# BLDC_Page2.net
KiCad netlist of a schematic drawn in Altium Designer
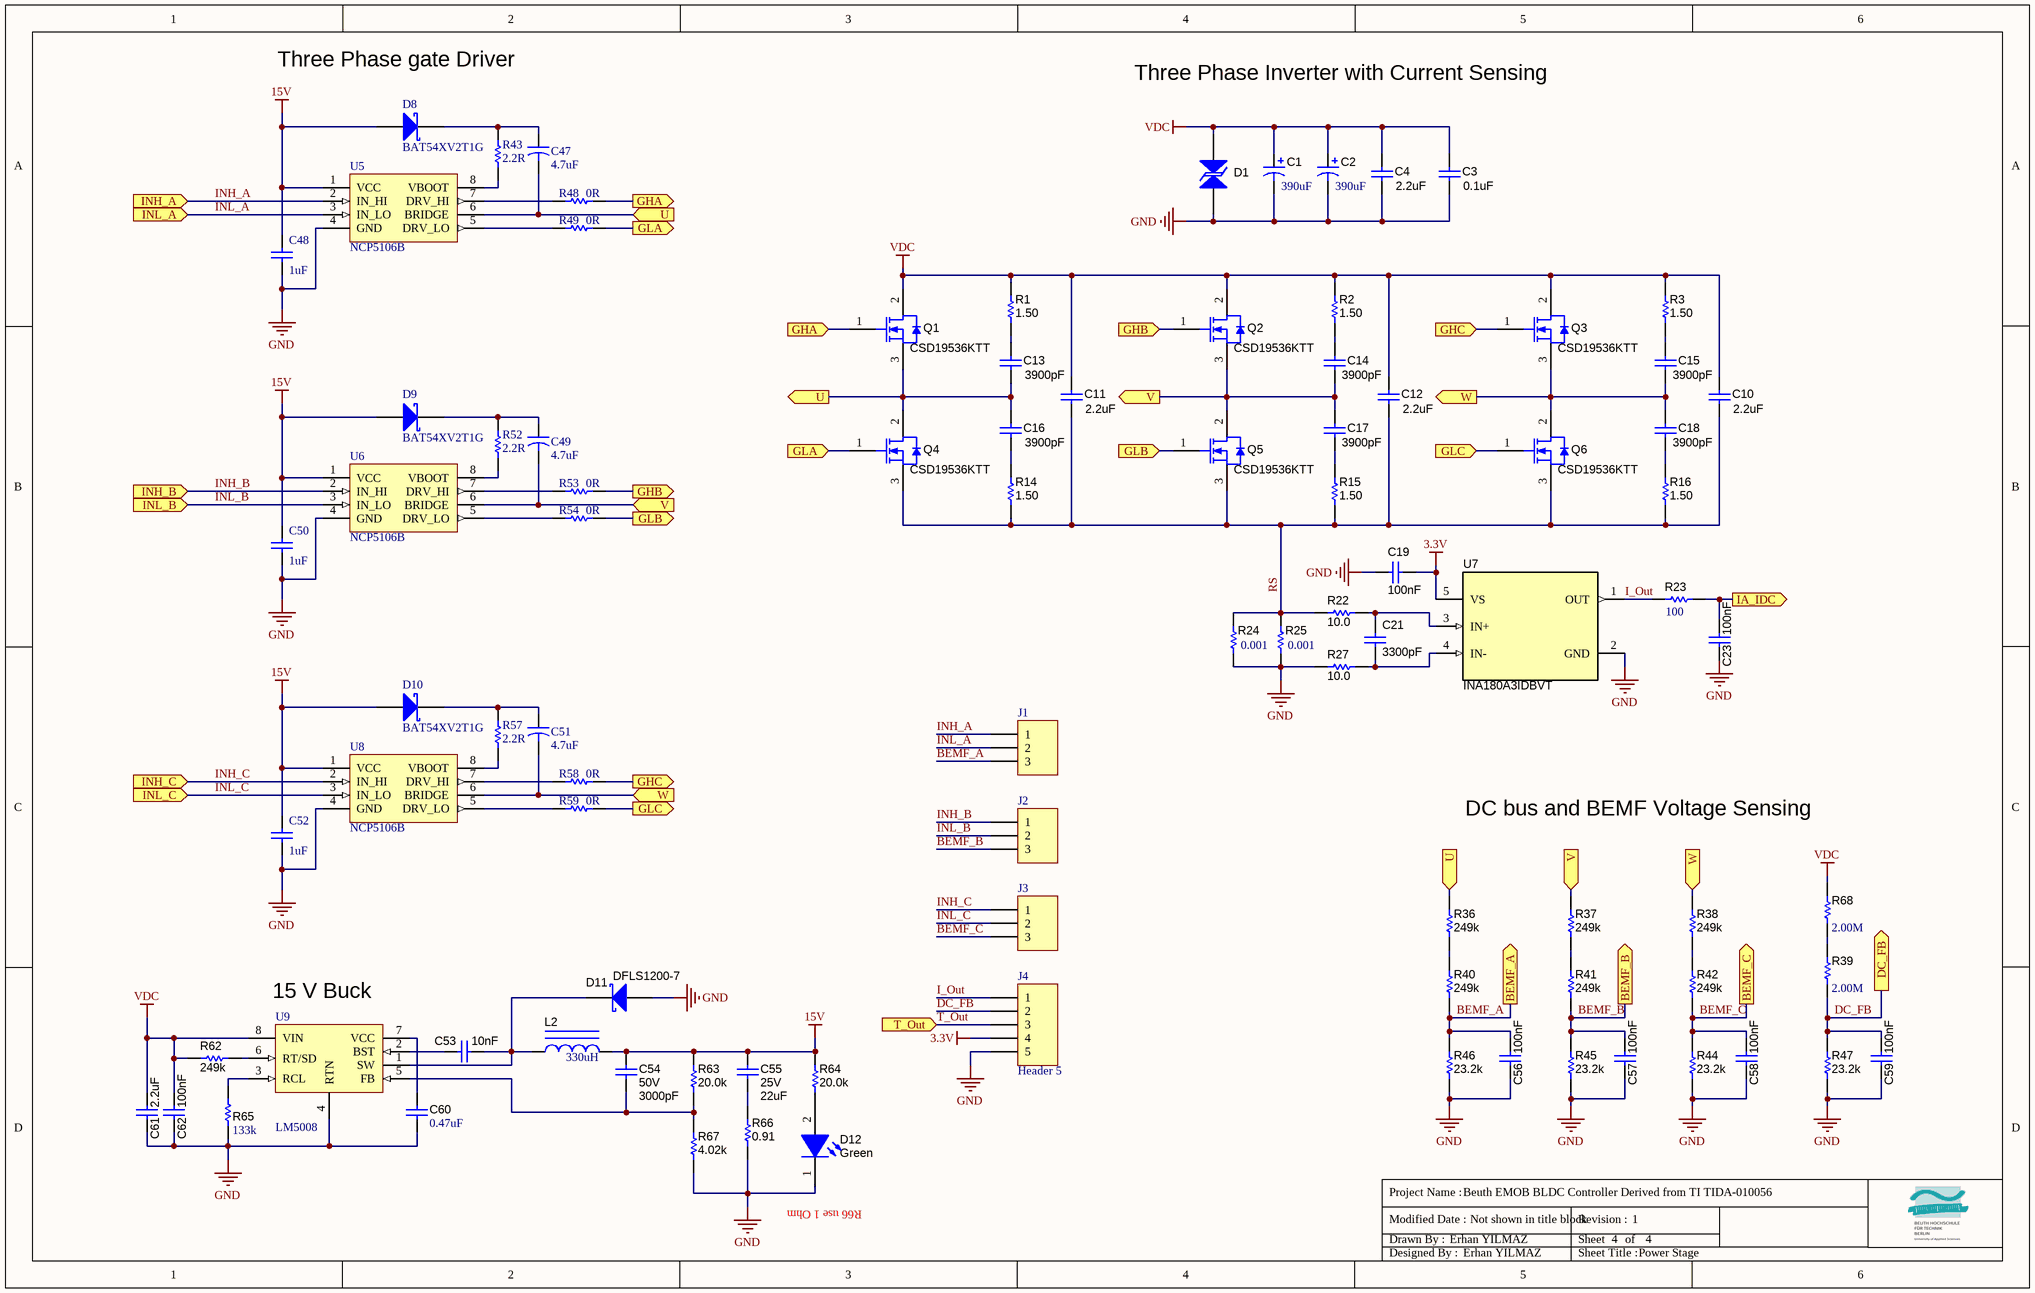
[diagram p0: BLDC_Page2.SchDoc]

(export (version "E")
  (design (tool "Eeschema 10.0.6"))
  (components
    (comp (ref "C1")
      (value "EEU-FS2A391")
      (footprint "YXJ_1600x2500")
      (description "CAP ALUM 390UF 20% 100V THRUHOLE")
      (fields
        (field (name "MANUFACTURER") "Panasonic Electronic Components")
        (field (name "VALUEDISPLAYED") "390uF")
        (field (name "PUBLISHER") "Texas Instruments")
      )
      (libsource (lib "Altium Vault - TI") (part "Cap_Polarized"))
    )
    (comp (ref "C2")
      (value "EEU-FS2A391")
      (footprint "YXJ_1600x2500")
      (description "CAP ALUM 390UF 20% 100V THRUHOLE")
      (fields
        (field (name "MANUFACTURER") "Panasonic Electronic Components")
        (field (name "VALUEDISPLAYED") "390uF")
        (field (name "PUBLISHER") "Texas Instruments")
      )
      (libsource (lib "Altium Vault - TI") (part "Cap_Polarized"))
    )
    (comp (ref "C3")
      (value "C3216X7R2A104K160AA")
      (footprint "1206")
      (description "CAP, CERM, 0.1 uF, 100 V, +/- 10%, X7R, 1206")
      (fields
        (field (name "MANUFACTURER") "TDK")
        (field (name "VALUEDISPLAYED") "0.1uF")
        (field (name "PUBLISHER") "Texas Instruments")
      )
      (libsource (lib "Altium Vault - TI") (part "Capacitor"))
    )
    (comp (ref "C4")
      (value "CL31B225KCHSNNE")
      (footprint "1206")
      (description "CAP CER 2.2UF 100V X7R 1206")
      (fields
        (field (name "MANUFACTURER") "Samsung Electro-Mechanics")
        (field (name "VALUEDISPLAYED") "2.2uF")
        (field (name "PUBLISHER") "Texas Instruments")
      )
      (libsource (lib "Altium Vault - TI") (part "Capacitor"))
    )
    (comp (ref "C10")
      (value "CL31B225KCHSNNE")
      (footprint "1206")
      (description "CAP CER 2.2UF 100V X7R 1206")
      (fields
        (field (name "MANUFACTURER") "Samsung Electro-Mechanics")
        (field (name "VALUEDISPLAYED") "2.2uF")
        (field (name "PUBLISHER") "Texas Instruments")
      )
      (libsource (lib "Altium Vault - TI") (part "Capacitor"))
    )
    (comp (ref "C11")
      (value "CL31B225KCHSNNE")
      (footprint "1206")
      (description "CAP CER 2.2UF 100V X7R 1206")
      (fields
        (field (name "MANUFACTURER") "Samsung Electro-Mechanics")
        (field (name "VALUEDISPLAYED") "2.2uF")
        (field (name "PUBLISHER") "Texas Instruments")
      )
      (libsource (lib "Altium Vault - TI") (part "Capacitor"))
    )
    (comp (ref "C12")
      (value "CL31B225KCHSNNE")
      (footprint "1206")
      (description "CAP CER 2.2UF 100V X7R 1206")
      (fields
        (field (name "MANUFACTURER") "Samsung Electro-Mechanics")
        (field (name "VALUEDISPLAYED") "2.2uF")
        (field (name "PUBLISHER") "Texas Instruments")
      )
      (libsource (lib "Altium Vault - TI") (part "Capacitor"))
    )
    (comp (ref "C13")
      (value "12061C392KAZ2A")
      (footprint "1206")
      (description "CAP CER 3900PF 100V X7R 1206")
      (fields
        (field (name "MANUFACTURER") "AVX Corporation")
        (field (name "VALUEDISPLAYED") "3900pF")
        (field (name "PUBLISHER") "Texas Instruments")
      )
      (libsource (lib "Altium Vault - TI") (part "Capacitor"))
    )
    (comp (ref "C14")
      (value "12061C392KAZ2A")
      (footprint "1206")
      (description "CAP CER 3900PF 100V X7R 1206")
      (fields
        (field (name "MANUFACTURER") "AVX Corporation")
        (field (name "VALUEDISPLAYED") "3900pF")
        (field (name "PUBLISHER") "Texas Instruments")
      )
      (libsource (lib "Altium Vault - TI") (part "Capacitor"))
    )
    (comp (ref "C15")
      (value "12061C392KAZ2A")
      (footprint "1206")
      (description "CAP CER 3900PF 100V X7R 1206")
      (fields
        (field (name "MANUFACTURER") "AVX Corporation")
        (field (name "VALUEDISPLAYED") "3900pF")
        (field (name "PUBLISHER") "Texas Instruments")
      )
      (libsource (lib "Altium Vault - TI") (part "Capacitor"))
    )
    (comp (ref "C16")
      (value "12061C392KAZ2A")
      (footprint "1206")
      (description "CAP CER 3900PF 100V X7R 1206")
      (fields
        (field (name "MANUFACTURER") "AVX Corporation")
        (field (name "VALUEDISPLAYED") "3900pF")
        (field (name "PUBLISHER") "Texas Instruments")
      )
      (libsource (lib "Altium Vault - TI") (part "Capacitor"))
    )
    (comp (ref "C17")
      (value "12061C392KAZ2A")
      (footprint "1206")
      (description "CAP CER 3900PF 100V X7R 1206")
      (fields
        (field (name "MANUFACTURER") "AVX Corporation")
        (field (name "VALUEDISPLAYED") "3900pF")
        (field (name "PUBLISHER") "Texas Instruments")
      )
      (libsource (lib "Altium Vault - TI") (part "Capacitor"))
    )
    (comp (ref "C18")
      (value "12061C392KAZ2A")
      (footprint "1206")
      (description "CAP CER 3900PF 100V X7R 1206")
      (fields
        (field (name "MANUFACTURER") "AVX Corporation")
        (field (name "VALUEDISPLAYED") "3900pF")
        (field (name "PUBLISHER") "Texas Instruments")
      )
      (libsource (lib "Altium Vault - TI") (part "Capacitor"))
    )
    (comp (ref "C19")
      (value "GRM1885C1H302JA01D")
      (footprint "0603")
      (description "CAP, CERM, 100 nF, 100 V, +/- 5%, C0G/NP0, 0603")
      (fields
        (field (name "MANUFACTURER") "MuRata")
        (field (name "VALUEDISPLAYED") "100nF")
        (field (name "PUBLISHER") "Texas Instruments")
      )
      (libsource (lib "Altium Vault - TI") (part "Capacitor"))
    )
    (comp (ref "C21")
      (value "3300pF")
      (footprint "0603")
      (description "CAP, CERM, 3300 pF, 50 V, +/- 10%, X7R, 0603")
      (fields
        (field (name "MANUFACTURER") "MuRata")
        (field (name "PARTNUMBER") "GRM155R71H332KA01D")
        (field (name "PUBLISHER") "Texas Instruments")
      )
      (libsource (lib "Altium Vault - TI") (part "Capacitor"))
    )
    (comp (ref "C23")
      (value "GRM1885C1H302JA01D")
      (footprint "0603")
      (description "CAP, CERM, 100 nF, 100 V, +/- 5%, C0G/NP0, 0603")
      (fields
        (field (name "MANUFACTURER") "MuRata")
        (field (name "VALUEDISPLAYED") "100nF")
        (field (name "PUBLISHER") "Texas Instruments")
      )
      (libsource (lib "Altium Vault - TI") (part "Capacitor"))
    )
    (comp (ref "C47")
      (value "4.7uF")
      (footprint "0805_HV")
      (description "4.7uF 25V Tantalum SMD Capacitor")
      (fields (field (name "MANUFACTURER") "AVX") (field (name "PUBLISHER") "Altium Limited"))
      (libsource (lib "Miscellaneous Devices") (part "Cap2"))
    )
    (comp (ref "C48")
      (value "1uF")
      (footprint "0603")
      (description "1uF %10 35V 0603")
      (fields (field (name "PUBLISHER") "Altium Limited"))
      (libsource (lib "Miscellaneous Devices") (part "Cap Semi"))
    )
    (comp (ref "C49")
      (value "4.7uF")
      (footprint "0805_HV")
      (description "4.7uF 25V Tantalum SMD Capacitor")
      (fields (field (name "MANUFACTURER") "AVX") (field (name "PUBLISHER") "Altium Limited"))
      (libsource (lib "Miscellaneous Devices") (part "Cap2"))
    )
    (comp (ref "C50")
      (value "1uF")
      (footprint "0603")
      (description "1uF %10 35V  0603")
      (fields (field (name "PUBLISHER") "Altium Limited"))
      (libsource (lib "Miscellaneous Devices") (part "Cap Semi"))
    )
    (comp (ref "C51")
      (value "4.7uF")
      (footprint "0805_HV")
      (description "4.7uF 25V Tantalum SMD Capacitor")
      (fields (field (name "MANUFACTURER") "AVX") (field (name "PUBLISHER") "Altium Limited"))
      (libsource (lib "Miscellaneous Devices") (part "Cap2"))
    )
    (comp (ref "C52")
      (value "1uF")
      (footprint "0603")
      (description "1uF %10 35V  0603")
      (fields (field (name "PUBLISHER") "Altium Limited"))
      (libsource (lib "Miscellaneous Devices") (part "Cap Semi"))
    )
    (comp (ref "C53")
      (value "885012206114")
      (footprint "0603")
      (description "CAP, CERM, 0.01 µF, 100 V,+/- 10%, X7R, 0603")
      (fields (field (name "MANUFACTURER") "Wurth Elektronik") (field (name "CAP_F") "10nF"))
      (libsource (lib "Altium Vault - TI") (part "Capacitor"))
    )
    (comp (ref "C54")
      (value "CAP, CERM, 3000 pF, 50 V, +/- 5%, C0G/NP0, 0603")
      (footprint "0603")
      (fields
        (field (name "MANUFACTURER") "MuRata")
        (field (name "PARTNUMBER") "GRM1885C1H302JA01D")
        (field (name "VDC_V") "50V")
        (field (name "VALUEDISPLAYED") "3000pF")
        (field (name "PUBLISHER") "Texas Instruments")
      )
      (libsource (lib "Altium Vault - TI") (part "Capacitor"))
    )
    (comp (ref "C55")
      (value "C2012X7R1H225K125AC")
      (footprint "1210_280")
      (description "CAP, CERM, 22 uF, 25 V, +/- 10%, X7R, 1210")
      (fields
        (field (name "MANUFACTURER") "TDK")
        (field (name "VDC_V") "25V")
        (field (name "VALUEDISPLAYED") "22uF")
        (field (name "PUBLISHER") "Texas Instruments")
      )
      (libsource (lib "Altium Vault - TI") (part "Capacitor"))
    )
    (comp (ref "C56")
      (value "GRM1885C1H302JA01D")
      (footprint "0603")
      (description "CAP, CERM, 100 nF, 100 V, +/- 5%, C0G/NP0, 0603")
      (fields
        (field (name "MANUFACTURER") "MuRata")
        (field (name "VALUEDISPLAYED") "100nF")
        (field (name "PUBLISHER") "Texas Instruments")
      )
      (libsource (lib "Altium Vault - TI") (part "Capacitor"))
    )
    (comp (ref "C57")
      (value "GRM1885C1H302JA01D")
      (footprint "0603")
      (description "CAP, CERM, 100 nF, 100 V, +/- 5%, C0G/NP0, 0603")
      (fields
        (field (name "MANUFACTURER") "MuRata")
        (field (name "VALUEDISPLAYED") "100nF")
        (field (name "PUBLISHER") "Texas Instruments")
      )
      (libsource (lib "Altium Vault - TI") (part "Capacitor"))
    )
    (comp (ref "C58")
      (value "GRM1885C1H302JA01D")
      (footprint "0603")
      (description "CAP, CERM, 100 nF, 100 V, +/- 5%, C0G/NP0, 0603")
      (fields
        (field (name "MANUFACTURER") "MuRata")
        (field (name "VALUEDISPLAYED") "100nF")
        (field (name "PUBLISHER") "Texas Instruments")
      )
      (libsource (lib "Altium Vault - TI") (part "Capacitor"))
    )
    (comp (ref "C59")
      (value "GRM1885C1H302JA01D")
      (footprint "0603")
      (description "CAP, CERM, 100 nF, 100 V, +/- 5%, C0G/NP0, 0603")
      (fields
        (field (name "MANUFACTURER") "MuRata")
        (field (name "VALUEDISPLAYED") "100nF")
        (field (name "PUBLISHER") "Texas Instruments")
      )
      (libsource (lib "Altium Vault - TI") (part "Capacitor"))
    )
    (comp (ref "C60")
      (value "CGB2A1X5R1C474K033BC")
      (footprint "0603")
      (description "CAP CER 0.47UF 16V X5R 0603")
      (fields
        (field (name "MANUFACTURER") "TDK Corporation")
        (field (name "VALUEDISPLAYED") "0.47uF")
        (field (name "PUBLISHER") "Texas Instruments")
      )
      (libsource (lib "Altium Vault - TI") (part "Capacitor"))
    )
    (comp (ref "C61")
      (value "C2012X7R1H225K125AC")
      (footprint "1206")
      (description "CAP, CERM, 2.2 uF, 100 V, +/- 10%, X7R, 1206")
      (fields
        (field (name "MANUFACTURER") "TDK")
        (field (name "VALUEDISPLAYED") "2.2uF")
        (field (name "PUBLISHER") "Texas Instruments")
      )
      (libsource (lib "Altium Vault - TI") (part "Capacitor"))
    )
    (comp (ref "C62")
      (value "GRM1885C1H302JA01D")
      (footprint "0603")
      (description "CAP, CERM, 100 nF, 100 V, +/- 5%, C0G/NP0, 0603")
      (fields
        (field (name "MANUFACTURER") "MuRata")
        (field (name "VALUEDISPLAYED") "100nF")
        (field (name "PUBLISHER") "Texas Instruments")
      )
      (libsource (lib "Altium Vault - TI") (part "Capacitor"))
    )
    (comp (ref "D1")
      (value "SMBJ70CA-13-F")
      (footprint "SMB-Bi")
      (description "Diode, TVS, Bi, 70 V, SMB")
      (fields (field (name "MANUFACTURER") "Diodes Inc."))
      (libsource (lib "Altium Vault - TI") (part "Diode_TVS_Bi"))
    )
    (comp (ref "D8")
      (value "BAT54XV2T1G")
      (footprint "SOD-523")
      (description "Schottky Diode")
      (fields (field (name "PUBLISHER") "Altium Limited"))
      (libsource (lib "Miscellaneous Devices") (part "D Schottky"))
    )
    (comp (ref "D9")
      (value "BAT54XV2T1G")
      (footprint "BLDC:SOD-523")
      (description "Schottky Diode")
      (fields (field (name "PUBLISHER") "Altium Limited"))
      (libsource (lib "Miscellaneous Devices") (part "D Schottky"))
    )
    (comp (ref "D10")
      (value "BAT54XV2T1G")
      (footprint "SOD-523")
      (description "Schottky Diode")
      (fields (field (name "PUBLISHER") "Altium Limited"))
      (libsource (lib "Miscellaneous Devices") (part "D Schottky"))
    )
    (comp (ref "D11")
      (value "DFLS1200-7")
      (footprint "PowerDI123")
      (description "Diode, Schottky, 200 V, 1 A, PowerDI123")
      (fields (field (name "MANUFACTURER") "Diodes Inc.") (field (name "PUBLISHER") "Texas Instruments"))
      (libsource (lib "Altium Vault - TI") (part "DIODE_SCHOTTKY"))
    )
    (comp (ref "D12")
      (value "Green")
      (footprint "WL-SMCW_GREEN")
      (description "LED, Green, SMD")
      (fields
        (field (name "MANUFACTURER") "Wurth Elektronik")
        (field (name "PARTNUMBER") "150060GS75000")
        (field (name "PUBLISHER") "Texas Instruments")
      )
      (libsource (lib "Altium Vault - TI") (part "LED_A2_K1"))
    )
    (comp (ref "J1")
      (value "Header 3")
      (footprint "HDR1X3")
      (description "Header, 3-Pin")
      (fields (field (name "PUBLISHER") "Altium Limited"))
      (libsource (lib "Miscellaneous Connectors") (part "Header 3"))
    )
    (comp (ref "J2")
      (value "Header 3")
      (footprint "HDR1X3")
      (description "Header, 3-Pin")
      (fields (field (name "PUBLISHER") "Altium Limited"))
      (libsource (lib "Miscellaneous Connectors") (part "Header 3"))
    )
    (comp (ref "J3")
      (value "Header 3")
      (footprint "HDR1X3")
      (description "Header, 3-Pin")
      (fields (field (name "PUBLISHER") "Altium Limited"))
      (libsource (lib "Miscellaneous Connectors") (part "Header 3"))
    )
    (comp (ref "J4")
      (value "Header 5")
      (footprint "HDR1X5")
      (description "Header, 5-Pin")
      (fields (field (name "PUBLISHER") "Altium Limited"))
      (libsource (lib "Miscellaneous Connectors") (part "Header 5"))
    )
    (comp (ref "L2")
      (value "SDR0604-331KL")
      (footprint "SDR0604")
      (description "Inductor, Drum Core, Ferrite, 330 uH, 0.27 A, 2.25 ohm, SMD")
      (fields
        (field (name "MANUFACTURER") "Bourns")
        (field (name "VALUEDISPLAYED") "330uH")
        (field (name "PUBLISHER") "Texas Instruments")
      )
      (libsource (lib "Altium Vault - TI") (part "Inductor_Iron"))
    )
    (comp (ref "Q1")
      (value "CSD19536KTT")
      (footprint "KTT0002A")
      (description "MOSFET, N-CH, 100 V, 200 A, KTT0002A (TO-263-2)")
      (fields (field (name "MANUFACTURER") "Texas Instruments"))
      (libsource (lib "Altium Vault - TI") (part "MOSFET_N_D2G1S3"))
    )
    (comp (ref "Q2")
      (value "CSD19536KTT")
      (footprint "KTT0002A")
      (description "MOSFET, N-CH, 100 V, 200 A, KTT0002A (TO-263-2)")
      (fields (field (name "MANUFACTURER") "Texas Instruments"))
      (libsource (lib "Altium Vault - TI") (part "MOSFET_N_D2G1S3"))
    )
    (comp (ref "Q3")
      (value "CSD19536KTT")
      (footprint "KTT0002A")
      (description "MOSFET, N-CH, 100 V, 200 A, KTT0002A (TO-263-2)")
      (fields (field (name "MANUFACTURER") "Texas Instruments"))
      (libsource (lib "Altium Vault - TI") (part "MOSFET_N_D2G1S3"))
    )
    (comp (ref "Q4")
      (value "CSD19536KTT")
      (footprint "KTT0002A")
      (description "MOSFET, N-CH, 100 V, 200 A, KTT0002A (TO-263-2)")
      (fields (field (name "MANUFACTURER") "Texas Instruments"))
      (libsource (lib "Altium Vault - TI") (part "MOSFET_N_D2G1S3"))
    )
    (comp (ref "Q5")
      (value "CSD19536KTT")
      (footprint "KTT0002A")
      (description "MOSFET, N-CH, 100 V, 200 A, KTT0002A (TO-263-2)")
      (fields (field (name "MANUFACTURER") "Texas Instruments"))
      (libsource (lib "Altium Vault - TI") (part "MOSFET_N_D2G1S3"))
    )
    (comp (ref "Q6")
      (value "CSD19536KTT")
      (footprint "KTT0002A")
      (description "MOSFET, N-CH, 100 V, 200 A, KTT0002A (TO-263-2)")
      (fields (field (name "MANUFACTURER") "Texas Instruments"))
      (libsource (lib "Altium Vault - TI") (part "MOSFET_N_D2G1S3"))
    )
    (comp (ref "R1")
      (value "CRCW12061R50FKEA")
      (footprint "1206")
      (description "RES, 1.50, 1%, 0.25 W, AEC-Q200 Grade 0, 1206")
      (fields (field (name "MANUFACTURER") "Vishay-Dale") (field (name "VALUEDISPLAYED") "1.50"))
      (libsource (lib "Altium Vault - TI") (part "Resistor"))
    )
    (comp (ref "R2")
      (value "CRCW12061R50FKEA")
      (footprint "1206")
      (description "RES, 1.50, 1%, 0.25 W, AEC-Q200 Grade 0, 1206")
      (fields (field (name "MANUFACTURER") "Vishay-Dale") (field (name "VALUEDISPLAYED") "1.50"))
      (libsource (lib "Altium Vault - TI") (part "Resistor"))
    )
    (comp (ref "R3")
      (value "CRCW12061R50FKEA")
      (footprint "1206")
      (description "RES, 1.50, 1%, 0.25 W, AEC-Q200 Grade 0, 1206")
      (fields (field (name "MANUFACTURER") "Vishay-Dale") (field (name "VALUEDISPLAYED") "1.50"))
      (libsource (lib "Altium Vault - TI") (part "Resistor"))
    )
    (comp (ref "R14")
      (value "CRCW12061R50FKEA")
      (footprint "1206")
      (description "RES, 1.50, 1%, 0.25 W, AEC-Q200 Grade 0, 1206")
      (fields (field (name "MANUFACTURER") "Vishay-Dale") (field (name "VALUEDISPLAYED") "1.50"))
      (libsource (lib "Altium Vault - TI") (part "Resistor"))
    )
    (comp (ref "R15")
      (value "CRCW12061R50FKEA")
      (footprint "1206")
      (description "RES, 1.50, 1%, 0.25 W, AEC-Q200 Grade 0, 1206")
      (fields (field (name "MANUFACTURER") "Vishay-Dale") (field (name "VALUEDISPLAYED") "1.50"))
      (libsource (lib "Altium Vault - TI") (part "Resistor"))
    )
    (comp (ref "R16")
      (value "CRCW12061R50FKEA")
      (footprint "1206")
      (description "RES, 1.50, 1%, 0.25 W, AEC-Q200 Grade 0, 1206")
      (fields (field (name "MANUFACTURER") "Vishay-Dale") (field (name "VALUEDISPLAYED") "1.50"))
      (libsource (lib "Altium Vault - TI") (part "Resistor"))
    )
    (comp (ref "R22")
      (value "CRCW040210R0FKED")
      (footprint "0603")
      (description "RES, 10.0, 1%, 0.063 W, AEC-Q200 Grade 0, 0603")
      (fields (field (name "MANUFACTURER") "Vishay-Dale") (field (name "VALUEDISPLAYED") "10.0"))
      (libsource (lib "Altium Vault - TI") (part "Resistor"))
    )
    (comp (ref "R23")
      (value "ERJ-2GEJ101X")
      (footprint "0603")
      (description "RES, 100, 5%, 0.1 W, AEC-Q200 Grade 0, 0603")
      (fields
        (field (name "MANUFACTURER") "Panasonic")
        (field (name "VALUEDISPLAYED") "100")
        (field (name "PUBLISHER") "Texas Instruments")
      )
      (libsource (lib "Altium Vault - TI") (part "Resistor"))
    )
    (comp (ref "R24")
      (value "CRE2512-FZ-R001E-3")
      (footprint "CRE2512-R1_R4")
      (description "RES, 0.001, 1%, 3 W, AEC-Q200 Grade 0, 2512")
      (fields
        (field (name "MANUFACTURER") "Bourns")
        (field (name "VALUEDISPLAYED") "0.001")
        (field (name "PUBLISHER") "Texas Instruments")
      )
      (libsource (lib "Altium Vault - TI") (part "Resistor"))
    )
    (comp (ref "R25")
      (value "0.001")
      (footprint "CRE2512-R1_R4")
      (description "RES, 0.001, 1%, 3 W, AEC-Q200 Grade 0, 2512")
      (fields
        (field (name "MANUFACTURER") "Bourns")
        (field (name "PARTNUMBER") "CRE2512-FZ-R001E-3")
        (field (name "PUBLISHER") "Texas Instruments")
      )
      (libsource (lib "Altium Vault - TI") (part "Resistor"))
    )
    (comp (ref "R27")
      (value "CRCW040210R0FKED")
      (footprint "0603")
      (description "RES, 10.0, 1%, 0.063 W, AEC-Q200 Grade 0, 0603")
      (fields (field (name "MANUFACTURER") "Vishay-Dale") (field (name "VALUEDISPLAYED") "10.0"))
      (libsource (lib "Altium Vault - TI") (part "Resistor"))
    )
    (comp (ref "R36")
      (value "RC0603FR-07249KL")
      (footprint "0603")
      (description "RES SMD 249K OHM 1% 1/16W 0603")
      (fields (field (name "MANUFACTURER") "Yageo") (field (name "VALUEDISPLAYED") "249k"))
      (libsource (lib "Altium Vault - TI") (part "Resistor"))
    )
    (comp (ref "R37")
      (value "RC0603FR-07249KL")
      (footprint "0603")
      (description "RES SMD 249K OHM 1% 1/16W 0603")
      (fields (field (name "MANUFACTURER") "Yageo") (field (name "VALUEDISPLAYED") "249k"))
      (libsource (lib "Altium Vault - TI") (part "Resistor"))
    )
    (comp (ref "R38")
      (value "RC0603FR-07249KL")
      (footprint "0603")
      (description "RES SMD 249K OHM 1% 1/16W 0603")
      (fields (field (name "MANUFACTURER") "Yageo") (field (name "VALUEDISPLAYED") "249k"))
      (libsource (lib "Altium Vault - TI") (part "Resistor"))
    )
    (comp (ref "R39")
      (value "CRCW06032M00FKED")
      (footprint "0603")
      (description "RES, 2.00 M, 1%, 0.063 W, AEC-Q200 Grade 0, 0603")
      (fields
        (field (name "MANUFACTURER") "Vishay-Dale")
        (field (name "PARTNUMBER") "CRCW04022M00FKED")
        (field (name "VALUEDISPLAYED") "2.00M")
      )
      (libsource (lib "Altium Vault - TI") (part "Resistor"))
    )
    (comp (ref "R40")
      (value "RC0603FR-07249KL")
      (footprint "0603")
      (description "RES SMD 249K OHM 1% 1/16W 0603")
      (fields (field (name "MANUFACTURER") "Yageo") (field (name "VALUEDISPLAYED") "249k"))
      (libsource (lib "Altium Vault - TI") (part "Resistor"))
    )
    (comp (ref "R41")
      (value "RC0603FR-07249KL")
      (footprint "0603")
      (description "RES SMD 249K OHM 1% 1/16W 0603")
      (fields (field (name "MANUFACTURER") "Yageo") (field (name "VALUEDISPLAYED") "249k"))
      (libsource (lib "Altium Vault - TI") (part "Resistor"))
    )
    (comp (ref "R42")
      (value "RC0603FR-07249KL")
      (footprint "0603")
      (description "RES SMD 249K OHM 1% 1/16W 0603")
      (fields (field (name "MANUFACTURER") "Yageo") (field (name "VALUEDISPLAYED") "249k"))
      (libsource (lib "Altium Vault - TI") (part "Resistor"))
    )
    (comp (ref "R43")
      (value "2.2R")
      (footprint "0603")
      (description "2.2R SMD 0.33w 0603")
      (fields (field (name "PUBLISHER") "Altium Limited"))
      (libsource (lib "Miscellaneous Devices") (part "Res1"))
    )
    (comp (ref "R44")
      (value "RC0603FR-0723K2L")
      (footprint "0603")
      (description "RES SMD 23.2K OHM 1% 1/16W 0603")
      (fields (field (name "MANUFACTURER") "Yageo") (field (name "VALUEDISPLAYED") "23.2k"))
      (libsource (lib "Altium Vault - TI") (part "Resistor"))
    )
    (comp (ref "R45")
      (value "RC0603FR-0723K2L")
      (footprint "0603")
      (description "RES SMD 23.2K OHM 1% 1/16W 0603")
      (fields (field (name "MANUFACTURER") "Yageo") (field (name "VALUEDISPLAYED") "23.2k"))
      (libsource (lib "Altium Vault - TI") (part "Resistor"))
    )
    (comp (ref "R46")
      (value "RC0603FR-0723K2L")
      (footprint "0603")
      (description "RES SMD 23.2K OHM 1% 1/16W 0603")
      (fields (field (name "MANUFACTURER") "Yageo") (field (name "VALUEDISPLAYED") "23.2k"))
      (libsource (lib "Altium Vault - TI") (part "Resistor"))
    )
    (comp (ref "R47")
      (value "RC0603FR-0723K2L")
      (footprint "0603")
      (description "RES SMD 23.2K OHM 1% 1/16W 0603")
      (fields (field (name "MANUFACTURER") "Yageo") (field (name "VALUEDISPLAYED") "23.2k"))
      (libsource (lib "Altium Vault - TI") (part "Resistor"))
    )
    (comp (ref "R48")
      (value "0R")
      (footprint "0603")
      (description "0R SMD 0.33w 0603")
      (fields (field (name "PUBLISHER") "Altium Limited"))
      (libsource (lib "Miscellaneous Devices") (part "Res1"))
    )
    (comp (ref "R49")
      (value "0R")
      (footprint "0603")
      (description "0R SMD 0.33w 0603")
      (fields (field (name "PUBLISHER") "Altium Limited"))
      (libsource (lib "Miscellaneous Devices") (part "Res1"))
    )
    (comp (ref "R52")
      (value "2.2R")
      (footprint "0603")
      (description "2.2R SMD 0.33w 0603")
      (fields (field (name "PUBLISHER") "Altium Limited"))
      (libsource (lib "Miscellaneous Devices") (part "Res1"))
    )
    (comp (ref "R53")
      (value "0R")
      (footprint "0603")
      (description "0R SMD 0.33w 0603")
      (fields (field (name "PUBLISHER") "Altium Limited"))
      (libsource (lib "Miscellaneous Devices") (part "Res1"))
    )
    (comp (ref "R54")
      (value "0R")
      (footprint "0603")
      (description "0R SMD 0.33w 0603")
      (fields (field (name "PUBLISHER") "Altium Limited"))
      (libsource (lib "Miscellaneous Devices") (part "Res1"))
    )
    (comp (ref "R57")
      (value "2.2R")
      (footprint "0603")
      (description "2.2R SMD 0.33w 0603")
      (fields (field (name "PUBLISHER") "Altium Limited"))
      (libsource (lib "Miscellaneous Devices") (part "Res1"))
    )
    (comp (ref "R58")
      (value "0R")
      (footprint "0603")
      (description "0R SMD 0.33w 0603")
      (fields (field (name "PUBLISHER") "Altium Limited"))
      (libsource (lib "Miscellaneous Devices") (part "Res1"))
    )
    (comp (ref "R59")
      (value "0R")
      (footprint "0603")
      (description "0R SMD 0.33w 0603")
      (fields (field (name "PUBLISHER") "Altium Limited"))
      (libsource (lib "Miscellaneous Devices") (part "Res1"))
    )
    (comp (ref "R62")
      (value "RC0603FR-07249KL")
      (footprint "0603")
      (description "RES SMD 249K OHM 1% 1/16W 0603")
      (fields
        (field (name "MANUFACTURER") "Yageo")
        (field (name "PARTNUMBER") "RC0402FR-07249KL")
        (field (name "VALUEDISPLAYED") "249k")
      )
      (libsource (lib "Altium Vault - TI") (part "Resistor"))
    )
    (comp (ref "R63")
      (value "CRCW060320K0FKED")
      (footprint "0603")
      (description "RES, 20.0 k, 1%, 0.063 W, AEC-Q200 Grade 0, 0603")
      (fields
        (field (name "MANUFACTURER") "Vishay-Dale")
        (field (name "PARTNUMBER") "CRCW040220K0FKED")
        (field (name "VALUEDISPLAYED") "20.0k")
      )
      (libsource (lib "Altium Vault - TI") (part "Resistor"))
    )
    (comp (ref "R64")
      (value "CRCW060320K0FKED")
      (footprint "0603")
      (description "RES, 20.0 k, 1%, 0.063 W, AEC-Q200 Grade 0, 0603")
      (fields
        (field (name "MANUFACTURER") "Vishay-Dale")
        (field (name "PARTNUMBER") "CRCW040220K0FKED")
        (field (name "VALUEDISPLAYED") "20.0k")
      )
      (libsource (lib "Altium Vault - TI") (part "Resistor"))
    )
    (comp (ref "R65")
      (value "AC0402FR-07133KL")
      (footprint "0603")
      (description "RES, 133 k, 1%, 0.063 W, AEC-Q200 Grade 0, 0603")
      (fields (field (name "MANUFACTURER") "Yageo America") (field (name "VALUEDISPLAYED") "133k"))
      (libsource (lib "Altium Vault - TI") (part "Resistor"))
    )
    (comp (ref "R66")
      (value "ERJ-2BQFR91X")
      (footprint "0603")
      (description "RES, 0.91, 1%, 0.125 W, 0603")
      (fields
        (field (name "MANUFACTURER") "Panasonic")
        (field (name "VALUEDISPLAYED") "0.91")
        (field (name "PUBLISHER") "Texas Instruments")
      )
      (libsource (lib "Altium Vault - TI") (part "Resistor"))
    )
    (comp (ref "R67")
      (value "RC0402FR-074K02L")
      (footprint "0603")
      (description "RES SMD 4.02K OHM 1% 1/16W 0603")
      (fields (field (name "MANUFACTURER") "Yageo") (field (name "VALUEDISPLAYED") "4.02k"))
      (libsource (lib "Altium Vault - TI") (part "Resistor"))
    )
    (comp (ref "R68")
      (value "CRCW06032M00FKED")
      (footprint "0603")
      (description "RES, 2.00 M, 1%, 0.063 W, AEC-Q200 Grade 0, 0603")
      (fields
        (field (name "MANUFACTURER") "Vishay-Dale")
        (field (name "PARTNUMBER") "CRCW04022M00FKED")
        (field (name "VALUEDISPLAYED") "2.00M")
      )
      (libsource (lib "Altium Vault - TI") (part "Resistor"))
    )
    (comp (ref "U5")
      (value "NCP5106B")
      (footprint "SO-8_L")
      (description "High Voltage, High and Low  Side Driver")
      (fields (field (name "MANUFACTURER") "On Semiconductor") (field (name "DESIGNER") "Erhan YILMAZ"))
      (libsource (lib "BLDC") (part "NCP5106B"))
    )
    (comp (ref "U6")
      (value "NCP5106B")
      (footprint "SO-8_L")
      (description "High Voltage, High and Low  Side Driver")
      (fields (field (name "MANUFACTURER") "On Semiconductor") (field (name "DESIGNER") "Erhan YILMAZ"))
      (libsource (lib "BLDC") (part "NCP5106B"))
    )
    (comp (ref "U7")
      (value "INA180A3IDBV")
      (footprint "sot23-5")
      (fields
        (field (name "MANUFACTURER") "Texas Instruments")
        (field (name "PARTNUMBER") "INA180A3IDBVT")
        (field (name "PUBLISHER") "Texas Instruments")
      )
      (libsource (lib "Altium Vault - TI") (part "INA180"))
    )
    (comp (ref "U8")
      (value "NCP5106B")
      (footprint "SO-8_L")
      (description "High Voltage, High and Low  Side Driver")
      (fields (field (name "MANUFACTURER") "On Semiconductor") (field (name "DESIGNER") "Erhan YILMAZ"))
      (libsource (lib "BLDC") (part "NCP5106B"))
    )
    (comp (ref "U9")
      (value "LM5008")
      (footprint "VSSOP8")
      (description "LM5008 95-V, 350-mA, Constant On-Time DC/DC Buck Switching Regulator")
      (fields (field (name "MANUFACTURER") "TI") (field (name "DESIGNER") "Erhan YILMAZ"))
      (libsource (lib "BLDC") (part "LM5008"))
    )
  )
  (nets
    (net (code "1") (name "/BEMF_A") (class "Default")
      (node (ref "C56") (pin "1") (pinfunction "1_1") (pintype "passive"))
      (node (ref "J1") (pin "3") (pinfunction "3_3") (pintype "passive"))
      (node (ref "R40") (pin "1") (pinfunction "1_1") (pintype "passive"))
      (node (ref "R46") (pin "2") (pinfunction "2_2") (pintype "passive"))
    )
    (net (code "2") (name "/BEMF_B") (class "Default")
      (node (ref "C57") (pin "1") (pinfunction "1_1") (pintype "passive"))
      (node (ref "J2") (pin "3") (pinfunction "3_3") (pintype "passive"))
      (node (ref "R41") (pin "1") (pinfunction "1_1") (pintype "passive"))
      (node (ref "R45") (pin "2") (pinfunction "2_2") (pintype "passive"))
    )
    (net (code "3") (name "/BEMF_C") (class "Default")
      (node (ref "C58") (pin "1") (pinfunction "1_1") (pintype "passive"))
      (node (ref "J3") (pin "3") (pinfunction "3_3") (pintype "passive"))
      (node (ref "R42") (pin "1") (pinfunction "1_1") (pintype "passive"))
      (node (ref "R44") (pin "2") (pinfunction "2_2") (pintype "passive"))
    )
    (net (code "4") (name "/DC_FB") (class "Default")
      (node (ref "C59") (pin "1") (pinfunction "1_1") (pintype "passive"))
      (node (ref "J4") (pin "2") (pinfunction "2_2") (pintype "passive"))
      (node (ref "R39") (pin "1") (pinfunction "1_1") (pintype "passive"))
      (node (ref "R47") (pin "2") (pinfunction "2_2") (pintype "passive"))
    )
    (net (code "5") (name "/GHA") (class "Default")
      (node (ref "Q1") (pin "1") (pinfunction "G_1") (pintype "passive"))
      (node (ref "R48") (pin "1") (pinfunction "1_1") (pintype "passive"))
    )
    (net (code "6") (name "/GHB") (class "Default")
      (node (ref "Q2") (pin "1") (pinfunction "G_1") (pintype "passive"))
      (node (ref "R53") (pin "1") (pinfunction "1_1") (pintype "passive"))
    )
    (net (code "7") (name "/GHC") (class "Default")
      (node (ref "Q3") (pin "1") (pinfunction "G_1") (pintype "passive"))
      (node (ref "R58") (pin "1") (pinfunction "1_1") (pintype "passive"))
    )
    (net (code "8") (name "/GLA") (class "Default")
      (node (ref "Q4") (pin "1") (pinfunction "G_1") (pintype "passive"))
      (node (ref "R49") (pin "1") (pinfunction "1_1") (pintype "passive"))
    )
    (net (code "9") (name "/GLB") (class "Default")
      (node (ref "Q5") (pin "1") (pinfunction "G_1") (pintype "passive"))
      (node (ref "R54") (pin "1") (pinfunction "1_1") (pintype "passive"))
    )
    (net (code "10") (name "/GLC") (class "Default")
      (node (ref "Q6") (pin "1") (pinfunction "G_1") (pintype "passive"))
      (node (ref "R59") (pin "1") (pinfunction "1_1") (pintype "passive"))
    )
    (net (code "11") (name "/IA_IDC") (class "Default")
      (node (ref "C23") (pin "1") (pinfunction "1_1") (pintype "passive"))
      (node (ref "R23") (pin "2") (pinfunction "2_2") (pintype "passive"))
    )
    (net (code "12") (name "/INH_A") (class "Default")
      (node (ref "J1") (pin "1") (pinfunction "1_1") (pintype "passive"))
      (node (ref "U5") (pin "2") (pinfunction "IN_HI_2") (pintype "input"))
    )
    (net (code "13") (name "/INH_B") (class "Default")
      (node (ref "J2") (pin "1") (pinfunction "1_1") (pintype "passive"))
      (node (ref "U6") (pin "2") (pinfunction "IN_HI_2") (pintype "input"))
    )
    (net (code "14") (name "/INH_C") (class "Default")
      (node (ref "J3") (pin "1") (pinfunction "1_1") (pintype "passive"))
      (node (ref "U8") (pin "2") (pinfunction "IN_HI_2") (pintype "input"))
    )
    (net (code "15") (name "/INL_A") (class "Default")
      (node (ref "J1") (pin "2") (pinfunction "2_2") (pintype "passive"))
      (node (ref "U5") (pin "3") (pinfunction "IN_LO_3") (pintype "input"))
    )
    (net (code "16") (name "/INL_B") (class "Default")
      (node (ref "J2") (pin "2") (pinfunction "2_2") (pintype "passive"))
      (node (ref "U6") (pin "3") (pinfunction "IN_LO_3") (pintype "input"))
    )
    (net (code "17") (name "/INL_C") (class "Default")
      (node (ref "J3") (pin "2") (pinfunction "2_2") (pintype "passive"))
      (node (ref "U8") (pin "3") (pinfunction "IN_LO_3") (pintype "input"))
    )
    (net (code "18") (name "/I_Out") (class "Default")
      (node (ref "J4") (pin "1") (pinfunction "1_1") (pintype "passive"))
      (node (ref "R23") (pin "1") (pinfunction "1_1") (pintype "passive"))
      (node (ref "U7") (pin "1") (pinfunction "OUT_1") (pintype "output"))
    )
    (net (code "19") (name "/RS") (class "Default")
      (node (ref "C10") (pin "2") (pinfunction "2_2") (pintype "passive"))
      (node (ref "C11") (pin "2") (pinfunction "2_2") (pintype "passive"))
      (node (ref "C12") (pin "2") (pinfunction "2_2") (pintype "passive"))
      (node (ref "Q4") (pin "3") (pinfunction "S_3") (pintype "passive"))
      (node (ref "Q5") (pin "3") (pinfunction "S_3") (pintype "passive"))
      (node (ref "Q6") (pin "3") (pinfunction "S_3") (pintype "passive"))
      (node (ref "R14") (pin "1") (pinfunction "1_1") (pintype "passive"))
      (node (ref "R15") (pin "1") (pinfunction "1_1") (pintype "passive"))
      (node (ref "R16") (pin "1") (pinfunction "1_1") (pintype "passive"))
      (node (ref "R22") (pin "1") (pinfunction "1_1") (pintype "passive"))
      (node (ref "R24") (pin "2") (pinfunction "2_2") (pintype "passive"))
      (node (ref "R25") (pin "2") (pinfunction "2_2") (pintype "passive"))
    )
    (net (code "20") (name "/T_Out") (class "Default")
      (node (ref "J4") (pin "3") (pinfunction "3_3") (pintype "passive"))
    )
    (net (code "21") (name "/U") (class "Default")
      (node (ref "C13") (pin "2") (pinfunction "2_2") (pintype "passive"))
      (node (ref "C16") (pin "1") (pinfunction "1_1") (pintype "passive"))
      (node (ref "C47") (pin "2") (pinfunction "2_2") (pintype "passive"))
      (node (ref "Q1") (pin "3") (pinfunction "S_3") (pintype "passive"))
      (node (ref "Q4") (pin "2") (pinfunction "D_2") (pintype "passive"))
      (node (ref "R36") (pin "2") (pinfunction "2_2") (pintype "passive"))
      (node (ref "U5") (pin "6") (pinfunction "BRIDGE_6") (pintype "power_in"))
    )
    (net (code "22") (name "/V") (class "Default")
      (node (ref "C14") (pin "2") (pinfunction "2_2") (pintype "passive"))
      (node (ref "C17") (pin "1") (pinfunction "1_1") (pintype "passive"))
      (node (ref "C49") (pin "2") (pinfunction "2_2") (pintype "passive"))
      (node (ref "Q2") (pin "3") (pinfunction "S_3") (pintype "passive"))
      (node (ref "Q5") (pin "2") (pinfunction "D_2") (pintype "passive"))
      (node (ref "R37") (pin "2") (pinfunction "2_2") (pintype "passive"))
      (node (ref "U6") (pin "6") (pinfunction "BRIDGE_6") (pintype "power_in"))
    )
    (net (code "23") (name "/W") (class "Default")
      (node (ref "C15") (pin "2") (pinfunction "2_2") (pintype "passive"))
      (node (ref "C18") (pin "1") (pinfunction "1_1") (pintype "passive"))
      (node (ref "C51") (pin "2") (pinfunction "2_2") (pintype "passive"))
      (node (ref "Q3") (pin "3") (pinfunction "S_3") (pintype "passive"))
      (node (ref "Q6") (pin "2") (pinfunction "D_2") (pintype "passive"))
      (node (ref "R38") (pin "2") (pinfunction "2_2") (pintype "passive"))
      (node (ref "U8") (pin "6") (pinfunction "BRIDGE_6") (pintype "power_in"))
    )
    (net (code "24") (name "3.3V") (class "Default")
      (node (ref "C19") (pin "2") (pinfunction "2_2") (pintype "passive"))
      (node (ref "J4") (pin "4") (pinfunction "4_4") (pintype "passive"))
      (node (ref "U7") (pin "5") (pinfunction "VS_5") (pintype "power_in"))
    )
    (net (code "25") (name "15V") (class "Default")
      (node (ref "C48") (pin "2") (pinfunction "2_2") (pintype "passive"))
      (node (ref "C50") (pin "2") (pinfunction "2_2") (pintype "passive"))
      (node (ref "C52") (pin "2") (pinfunction "2_2") (pintype "passive"))
      (node (ref "C54") (pin "1") (pinfunction "1_1") (pintype "passive"))
      (node (ref "C55") (pin "1") (pinfunction "1_1") (pintype "passive"))
      (node (ref "D10") (pin "1") (pinfunction "A_1") (pintype "passive"))
      (node (ref "D8") (pin "1") (pinfunction "A_1") (pintype "passive"))
      (node (ref "D9") (pin "1") (pinfunction "A_1") (pintype "passive"))
      (node (ref "L2") (pin "2") (pinfunction "2_2") (pintype "passive"))
      (node (ref "R63") (pin "2") (pinfunction "2_2") (pintype "passive"))
      (node (ref "R64") (pin "2") (pinfunction "2_2") (pintype "passive"))
      (node (ref "U5") (pin "1") (pinfunction "VCC_1") (pintype "power_in"))
      (node (ref "U6") (pin "1") (pinfunction "VCC_1") (pintype "power_in"))
      (node (ref "U8") (pin "1") (pinfunction "VCC_1") (pintype "power_in"))
    )
    (net (code "26") (name "GND") (class "Default")
      (node (ref "C1") (pin "2") (pinfunction "-_2") (pintype "passive"))
      (node (ref "C19") (pin "1") (pinfunction "1_1") (pintype "passive"))
      (node (ref "C2") (pin "2") (pinfunction "-_2") (pintype "passive"))
      (node (ref "C23") (pin "2") (pinfunction "2_2") (pintype "passive"))
      (node (ref "C3") (pin "2") (pinfunction "2_2") (pintype "passive"))
      (node (ref "C4") (pin "2") (pinfunction "2_2") (pintype "passive"))
      (node (ref "C48") (pin "1") (pinfunction "1_1") (pintype "passive"))
      (node (ref "C50") (pin "1") (pinfunction "1_1") (pintype "passive"))
      (node (ref "C52") (pin "1") (pinfunction "1_1") (pintype "passive"))
      (node (ref "C56") (pin "2") (pinfunction "2_2") (pintype "passive"))
      (node (ref "C57") (pin "2") (pinfunction "2_2") (pintype "passive"))
      (node (ref "C58") (pin "2") (pinfunction "2_2") (pintype "passive"))
      (node (ref "C59") (pin "2") (pinfunction "2_2") (pintype "passive"))
      (node (ref "C60") (pin "1") (pinfunction "1_1") (pintype "passive"))
      (node (ref "C61") (pin "2") (pinfunction "2_2") (pintype "passive"))
      (node (ref "C62") (pin "2") (pinfunction "2_2") (pintype "passive"))
      (node (ref "D1") (pin "1") (pinfunction "1_1") (pintype "passive"))
      (node (ref "D11") (pin "2") (pinfunction "A_2") (pintype "passive"))
      (node (ref "D12") (pin "1") (pinfunction "K_1") (pintype "passive"))
      (node (ref "J4") (pin "5") (pinfunction "5_5") (pintype "passive"))
      (node (ref "R24") (pin "1") (pinfunction "1_1") (pintype "passive"))
      (node (ref "R25") (pin "1") (pinfunction "1_1") (pintype "passive"))
      (node (ref "R27") (pin "1") (pinfunction "1_1") (pintype "passive"))
      (node (ref "R44") (pin "1") (pinfunction "1_1") (pintype "passive"))
      (node (ref "R45") (pin "1") (pinfunction "1_1") (pintype "passive"))
      (node (ref "R46") (pin "1") (pinfunction "1_1") (pintype "passive"))
      (node (ref "R47") (pin "1") (pinfunction "1_1") (pintype "passive"))
      (node (ref "R65") (pin "1") (pinfunction "1_1") (pintype "passive"))
      (node (ref "R66") (pin "1") (pinfunction "1_1") (pintype "passive"))
      (node (ref "R67") (pin "1") (pinfunction "1_1") (pintype "passive"))
      (node (ref "U5") (pin "4") (pinfunction "GND_4") (pintype "power_in"))
      (node (ref "U6") (pin "4") (pinfunction "GND_4") (pintype "power_in"))
      (node (ref "U7") (pin "2") (pinfunction "GND_2") (pintype "power_in"))
      (node (ref "U8") (pin "4") (pinfunction "GND_4") (pintype "power_in"))
      (node (ref "U9") (pin "4") (pinfunction "RTN_4") (pintype "power_in"))
    )
    (net (code "27") (name "Net-(C13-Pad1)") (class "Default")
      (node (ref "C13") (pin "1") (pinfunction "1_1") (pintype "passive"))
      (node (ref "R1") (pin "1") (pinfunction "1_1") (pintype "passive"))
    )
    (net (code "28") (name "Net-(C14-Pad1)") (class "Default")
      (node (ref "C14") (pin "1") (pinfunction "1_1") (pintype "passive"))
      (node (ref "R2") (pin "1") (pinfunction "1_1") (pintype "passive"))
    )
    (net (code "29") (name "Net-(C15-Pad1)") (class "Default")
      (node (ref "C15") (pin "1") (pinfunction "1_1") (pintype "passive"))
      (node (ref "R3") (pin "1") (pinfunction "1_1") (pintype "passive"))
    )
    (net (code "30") (name "Net-(C16-Pad2)") (class "Default")
      (node (ref "C16") (pin "2") (pinfunction "2_2") (pintype "passive"))
      (node (ref "R14") (pin "2") (pinfunction "2_2") (pintype "passive"))
    )
    (net (code "31") (name "Net-(C17-Pad2)") (class "Default")
      (node (ref "C17") (pin "2") (pinfunction "2_2") (pintype "passive"))
      (node (ref "R15") (pin "2") (pinfunction "2_2") (pintype "passive"))
    )
    (net (code "32") (name "Net-(C18-Pad2)") (class "Default")
      (node (ref "C18") (pin "2") (pinfunction "2_2") (pintype "passive"))
      (node (ref "R16") (pin "2") (pinfunction "2_2") (pintype "passive"))
    )
    (net (code "33") (name "Net-(C55-Pad2)") (class "Default")
      (node (ref "C55") (pin "2") (pinfunction "2_2") (pintype "passive"))
      (node (ref "R66") (pin "2") (pinfunction "2_2") (pintype "passive"))
    )
    (net (code "34") (name "Net-(D8-K)") (class "Default")
      (node (ref "C47") (pin "1") (pinfunction "1_1") (pintype "passive"))
      (node (ref "D8") (pin "2") (pinfunction "K_2") (pintype "passive"))
      (node (ref "R43") (pin "2") (pinfunction "2_2") (pintype "passive"))
    )
    (net (code "35") (name "Net-(D9-K)") (class "Default")
      (node (ref "C49") (pin "1") (pinfunction "1_1") (pintype "passive"))
      (node (ref "D9") (pin "2") (pinfunction "K_2") (pintype "passive"))
      (node (ref "R52") (pin "2") (pinfunction "2_2") (pintype "passive"))
    )
    (net (code "36") (name "Net-(D10-K)") (class "Default")
      (node (ref "C51") (pin "1") (pinfunction "1_1") (pintype "passive"))
      (node (ref "D10") (pin "2") (pinfunction "K_2") (pintype "passive"))
      (node (ref "R57") (pin "2") (pinfunction "2_2") (pintype "passive"))
    )
    (net (code "37") (name "Net-(D11-K)") (class "Default")
      (node (ref "C53") (pin "2") (pinfunction "2_2") (pintype "passive"))
      (node (ref "D11") (pin "1") (pinfunction "K_1") (pintype "passive"))
      (node (ref "L2") (pin "1") (pinfunction "1_1") (pintype "passive"))
      (node (ref "U9") (pin "1") (pinfunction "SW_1") (pintype "power_in"))
    )
    (net (code "38") (name "Net-(D12-A)") (class "Default")
      (node (ref "D12") (pin "2") (pinfunction "A_2") (pintype "passive"))
      (node (ref "R64") (pin "1") (pinfunction "1_1") (pintype "passive"))
    )
    (net (code "39") (name "Net-(R36-Pad1)") (class "Default")
      (node (ref "R36") (pin "1") (pinfunction "1_1") (pintype "passive"))
      (node (ref "R40") (pin "2") (pinfunction "2_2") (pintype "passive"))
    )
    (net (code "40") (name "Net-(R37-Pad1)") (class "Default")
      (node (ref "R37") (pin "1") (pinfunction "1_1") (pintype "passive"))
      (node (ref "R41") (pin "2") (pinfunction "2_2") (pintype "passive"))
    )
    (net (code "41") (name "Net-(R38-Pad1)") (class "Default")
      (node (ref "R38") (pin "1") (pinfunction "1_1") (pintype "passive"))
      (node (ref "R42") (pin "2") (pinfunction "2_2") (pintype "passive"))
    )
    (net (code "42") (name "Net-(R39-Pad2)") (class "Default")
      (node (ref "R39") (pin "2") (pinfunction "2_2") (pintype "passive"))
      (node (ref "R68") (pin "1") (pinfunction "1_1") (pintype "passive"))
    )
    (net (code "43") (name "Net-(U5-DRV_HI)") (class "Default")
      (node (ref "R48") (pin "2") (pinfunction "2_2") (pintype "passive"))
      (node (ref "U5") (pin "7") (pinfunction "DRV_HI_7") (pintype "output"))
    )
    (net (code "44") (name "Net-(U5-DRV_LO)") (class "Default")
      (node (ref "R49") (pin "2") (pinfunction "2_2") (pintype "passive"))
      (node (ref "U5") (pin "5") (pinfunction "DRV_LO_5") (pintype "output"))
    )
    (net (code "45") (name "Net-(U5-VBOOT)") (class "Default")
      (node (ref "R43") (pin "1") (pinfunction "1_1") (pintype "passive"))
      (node (ref "U5") (pin "8") (pinfunction "VBOOT_8") (pintype "power_in"))
    )
    (net (code "46") (name "Net-(U6-DRV_HI)") (class "Default")
      (node (ref "R53") (pin "2") (pinfunction "2_2") (pintype "passive"))
      (node (ref "U6") (pin "7") (pinfunction "DRV_HI_7") (pintype "output"))
    )
    (net (code "47") (name "Net-(U6-DRV_LO)") (class "Default")
      (node (ref "R54") (pin "2") (pinfunction "2_2") (pintype "passive"))
      (node (ref "U6") (pin "5") (pinfunction "DRV_LO_5") (pintype "output"))
    )
    (net (code "48") (name "Net-(U6-VBOOT)") (class "Default")
      (node (ref "R52") (pin "1") (pinfunction "1_1") (pintype "passive"))
      (node (ref "U6") (pin "8") (pinfunction "VBOOT_8") (pintype "power_in"))
    )
    (net (code "49") (name "Net-(U7-IN+)") (class "Default")
      (node (ref "C21") (pin "1") (pinfunction "1_1") (pintype "passive"))
      (node (ref "R22") (pin "2") (pinfunction "2_2") (pintype "passive"))
      (node (ref "U7") (pin "3") (pinfunction "IN+_3") (pintype "input"))
    )
    (net (code "50") (name "Net-(U7-IN-)") (class "Default")
      (node (ref "C21") (pin "2") (pinfunction "2_2") (pintype "passive"))
      (node (ref "R27") (pin "2") (pinfunction "2_2") (pintype "passive"))
      (node (ref "U7") (pin "4") (pinfunction "IN-_4") (pintype "input"))
    )
    (net (code "51") (name "Net-(U8-DRV_HI)") (class "Default")
      (node (ref "R58") (pin "2") (pinfunction "2_2") (pintype "passive"))
      (node (ref "U8") (pin "7") (pinfunction "DRV_HI_7") (pintype "output"))
    )
    (net (code "52") (name "Net-(U8-DRV_LO)") (class "Default")
      (node (ref "R59") (pin "2") (pinfunction "2_2") (pintype "passive"))
      (node (ref "U8") (pin "5") (pinfunction "DRV_LO_5") (pintype "output"))
    )
    (net (code "53") (name "Net-(U8-VBOOT)") (class "Default")
      (node (ref "R57") (pin "1") (pinfunction "1_1") (pintype "passive"))
      (node (ref "U8") (pin "8") (pinfunction "VBOOT_8") (pintype "power_in"))
    )
    (net (code "54") (name "Net-(U9-BST)") (class "Default")
      (node (ref "C53") (pin "1") (pinfunction "1_1") (pintype "passive"))
      (node (ref "U9") (pin "2") (pinfunction "BST_2") (pintype "input"))
    )
    (net (code "55") (name "Net-(U9-FB)") (class "Default")
      (node (ref "C54") (pin "2") (pinfunction "2_2") (pintype "passive"))
      (node (ref "R63") (pin "1") (pinfunction "1_1") (pintype "passive"))
      (node (ref "R67") (pin "2") (pinfunction "2_2") (pintype "passive"))
      (node (ref "U9") (pin "5") (pinfunction "FB_5") (pintype "input"))
    )
    (net (code "56") (name "Net-(U9-RCL)") (class "Default")
      (node (ref "R65") (pin "2") (pinfunction "2_2") (pintype "passive"))
      (node (ref "U9") (pin "3") (pinfunction "RCL_3") (pintype "input"))
    )
    (net (code "57") (name "Net-(U9-RT{slash}SD)") (class "Default")
      (node (ref "R62") (pin "1") (pinfunction "1_1") (pintype "passive"))
      (node (ref "U9") (pin "6") (pinfunction "RT/SD_6") (pintype "input"))
    )
    (net (code "58") (name "Net-(U9-VCC)") (class "Default")
      (node (ref "C60") (pin "2") (pinfunction "2_2") (pintype "passive"))
      (node (ref "U9") (pin "7") (pinfunction "VCC_7") (pintype "power_in"))
    )
    (net (code "59") (name "VDC") (class "Default")
      (node (ref "C1") (pin "1") (pinfunction "+_1") (pintype "passive"))
      (node (ref "C10") (pin "1") (pinfunction "1_1") (pintype "passive"))
      (node (ref "C11") (pin "1") (pinfunction "1_1") (pintype "passive"))
      (node (ref "C12") (pin "1") (pinfunction "1_1") (pintype "passive"))
      (node (ref "C2") (pin "1") (pinfunction "+_1") (pintype "passive"))
      (node (ref "C3") (pin "1") (pinfunction "1_1") (pintype "passive"))
      (node (ref "C4") (pin "1") (pinfunction "1_1") (pintype "passive"))
      (node (ref "C61") (pin "1") (pinfunction "1_1") (pintype "passive"))
      (node (ref "C62") (pin "1") (pinfunction "1_1") (pintype "passive"))
      (node (ref "D1") (pin "2") (pinfunction "2_2") (pintype "passive"))
      (node (ref "Q1") (pin "2") (pinfunction "D_2") (pintype "passive"))
      (node (ref "Q2") (pin "2") (pinfunction "D_2") (pintype "passive"))
      (node (ref "Q3") (pin "2") (pinfunction "D_2") (pintype "passive"))
      (node (ref "R1") (pin "2") (pinfunction "2_2") (pintype "passive"))
      (node (ref "R2") (pin "2") (pinfunction "2_2") (pintype "passive"))
      (node (ref "R3") (pin "2") (pinfunction "2_2") (pintype "passive"))
      (node (ref "R62") (pin "2") (pinfunction "2_2") (pintype "passive"))
      (node (ref "R68") (pin "2") (pinfunction "2_2") (pintype "passive"))
      (node (ref "U9") (pin "8") (pinfunction "VIN_8") (pintype "power_in"))
    )
  )
)
